# sensors.net
KiCad netlist of a schematic drawn in Altium Designer
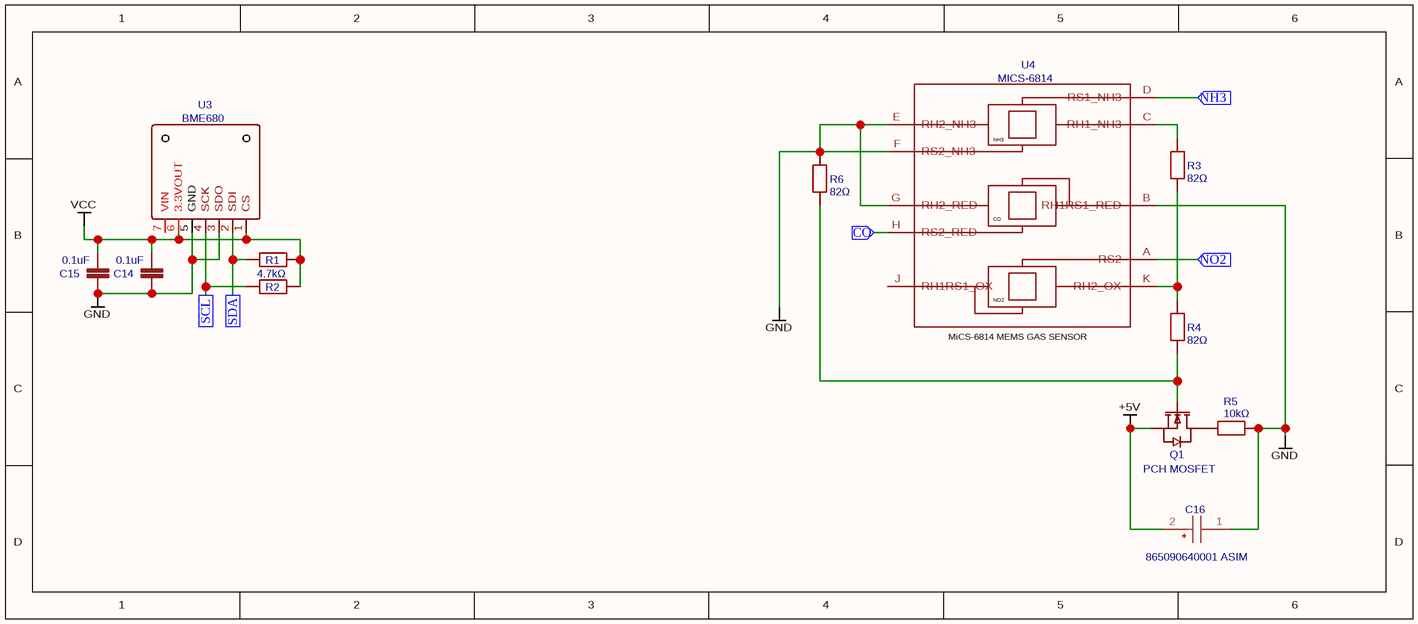
[diagram p0: sensors.schdoc]

(export (version "E")
  (design (tool "Eeschema 10.0.6"))
  (components
    (comp (ref "C14")
      (value "0.1uF")
      (description "CAP-00810")
      (fields (field (name "CONTRIBUTOR") "SparkFun"))
      (libsource (lib "altium-import") (part "root_0_0.1uF_"))
    )
    (comp (ref "C15")
      (value "0.1uF")
      (description "CAP-00810")
      (fields (field (name "CONTRIBUTOR") "SparkFun"))
      (libsource (lib "altium-import") (part "root_0_0.1uF_"))
    )
    (comp (ref "C16")
      (value "865090640001 ASIM")
      (fields (field (name "CONTRIBUTOR") "Rajesh Kumar"))
      (libsource (lib "altium-import") (part "root_2_865090640001 ASIM_"))
    )
    (comp (ref "Q1")
      (value "PCH MOSFET")
      (fields
        (field (name "BOM_SUPPLIER PART") "C516873")
        (field (name "BOM_MANUFACTURER PART") "VB1240B")
        (field (name "CONTRIBUTOR") "LCSC")
      )
      (libsource (lib "altium-import") (part "root_3_PCH MOSFET_"))
    )
    (comp (ref "R1")
      (value "4.7kΩ")
      (fields
        (field (name "BOM_SUPPLIER PART") "C517493")
        (field (name "BOM_MANUFACTURER PART") "TC0350D4701T5H")
        (field (name "CONTRIBUTOR") "LCSC")
      )
      (libsource (lib "altium-import") (part "root_2_4.7kΩ_"))
    )
    (comp (ref "R2")
      (value "4.7kΩ")
      (fields
        (field (name "BOM_SUPPLIER PART") "C517493")
        (field (name "BOM_MANUFACTURER PART") "TC0350D4701T5H")
        (field (name "CONTRIBUTOR") "LCSC")
      )
      (libsource (lib "altium-import") (part "root_2_4.7kΩ_"))
    )
    (comp (ref "R3")
      (value "82Ω")
      (fields
        (field (name "BOM_SUPPLIER PART") "C525388")
        (field (name "BOM_MANUFACTURER PART") "TCTR0603F47K0F3960T")
        (field (name "CONTRIBUTOR") "LCSC")
      )
      (libsource (lib "altium-import") (part "root_1_82Ω_"))
    )
    (comp (ref "R4")
      (value "82Ω")
      (fields
        (field (name "BOM_SUPPLIER PART") "C525388")
        (field (name "BOM_MANUFACTURER PART") "TCTR0603F47K0F3960T")
        (field (name "CONTRIBUTOR") "LCSC")
      )
      (libsource (lib "altium-import") (part "root_1_82Ω_"))
    )
    (comp (ref "R5")
      (value "10kΩ")
      (fields
        (field (name "BOM_SUPPLIER PART") "C525388")
        (field (name "BOM_MANUFACTURER PART") "TCTR0603F47K0F3960T")
        (field (name "CONTRIBUTOR") "LCSC")
      )
      (libsource (lib "altium-import") (part "root_2_10kΩ_"))
    )
    (comp (ref "R6")
      (value "82Ω")
      (fields
        (field (name "BOM_SUPPLIER PART") "C525388")
        (field (name "BOM_MANUFACTURER PART") "TCTR0603F47K0F3960T")
        (field (name "CONTRIBUTOR") "LCSC")
      )
      (libsource (lib "altium-import") (part "root_3_82Ω_"))
    )
    (comp (ref "U3")
      (value "BME680")
      (fields (field (name "BOM_SUPPLIER PART") "C125972") (field (name "CONTRIBUTOR") "mecopela"))
      (libsource (lib "altium-import") (part "root_1_BME680_"))
    )
    (comp (ref "U4")
      (value "MICS-6814")
      (description "314100015")
      (fields (field (name "CONTRIBUTOR") "sozturk"))
      (libsource (lib "altium-import") (part "root_0_MICS-6814_"))
    )
  )
  (nets
    (net (code "1") (name "+5V") (class "Default")
      (node (ref "C16") (pin "2") (pinfunction "-_2") (pintype "passive"))
      (node (ref "Q1") (pin "2") (pinfunction "S_2") (pintype "passive"))
    )
    (net (code "2") (name "/CO") (class "Default")
      (node (ref "U4") (pin "H") (pinfunction "RS2_RED_H") (pintype "passive"))
    )
    (net (code "3") (name "/NH3") (class "Default")
      (node (ref "U4") (pin "D") (pinfunction "RS1_NH3_D") (pintype "passive"))
    )
    (net (code "4") (name "/NO2") (class "Default")
      (node (ref "U4") (pin "A") (pinfunction "RS2_A") (pintype "passive"))
    )
    (net (code "5") (name "/SCL") (class "Default")
      (node (ref "R2") (pin "2") (pinfunction "2_2") (pintype "passive"))
      (node (ref "U3") (pin "4") (pinfunction "SCK_4") (pintype "passive"))
    )
    (net (code "6") (name "/SDA") (class "Default")
      (node (ref "R1") (pin "2") (pinfunction "2_2") (pintype "passive"))
      (node (ref "U3") (pin "2") (pinfunction "SDI_2") (pintype "passive"))
    )
    (net (code "7") (name "GND") (class "Default")
      (node (ref "C14") (pin "2") (pinfunction "2_2") (pintype "passive"))
      (node (ref "C15") (pin "2") (pinfunction "2_2") (pintype "passive"))
      (node (ref "C16") (pin "1") (pinfunction "+_1") (pintype "passive"))
      (node (ref "R5") (pin "1") (pinfunction "1_1") (pintype "passive"))
      (node (ref "R6") (pin "1") (pinfunction "1_1") (pintype "passive"))
      (node (ref "U3") (pin "3") (pinfunction "SDO_3") (pintype "passive"))
      (node (ref "U3") (pin "5") (pinfunction "GND_5") (pintype "passive"))
      (node (ref "U4") (pin "B") (pinfunction "RH1RS1_RED_B") (pintype "passive"))
      (node (ref "U4") (pin "E") (pinfunction "RH2_NH3_E") (pintype "passive"))
      (node (ref "U4") (pin "F") (pinfunction "RS2_NH3_F") (pintype "passive"))
      (node (ref "U4") (pin "G") (pinfunction "RH2_RED_G") (pintype "passive"))
    )
    (net (code "8") (name "Net-(Q1-D)") (class "Default")
      (node (ref "Q1") (pin "3") (pinfunction "D_3") (pintype "passive"))
      (node (ref "R5") (pin "2") (pinfunction "2_2") (pintype "passive"))
    )
    (net (code "9") (name "Net-(Q1-G)") (class "Default")
      (node (ref "Q1") (pin "1") (pinfunction "G_1") (pintype "passive"))
      (node (ref "R4") (pin "1") (pinfunction "1_1") (pintype "passive"))
      (node (ref "R6") (pin "2") (pinfunction "2_2") (pintype "passive"))
    )
    (net (code "10") (name "Net-(U4-RH1_NH3)") (class "Default")
      (node (ref "R3") (pin "2") (pinfunction "2_2") (pintype "passive"))
      (node (ref "U4") (pin "C") (pinfunction "RH1_NH3_C") (pintype "passive"))
    )
    (net (code "11") (name "Net-(U4-RH2_OX)") (class "Default")
      (node (ref "R3") (pin "1") (pinfunction "1_1") (pintype "passive"))
      (node (ref "R4") (pin "2") (pinfunction "2_2") (pintype "passive"))
      (node (ref "U4") (pin "K") (pinfunction "RH2_OX_K") (pintype "passive"))
    )
    (net (code "12") (name "VCC") (class "Default")
      (node (ref "C14") (pin "1") (pinfunction "1_1") (pintype "passive"))
      (node (ref "C15") (pin "1") (pinfunction "1_1") (pintype "passive"))
      (node (ref "R1") (pin "1") (pinfunction "1_1") (pintype "passive"))
      (node (ref "R2") (pin "1") (pinfunction "1_1") (pintype "passive"))
      (node (ref "U3") (pin "1") (pinfunction "CS_1") (pintype "passive"))
      (node (ref "U3") (pin "6") (pinfunction "3.3VOUT_6") (pintype "passive"))
    )
    (net (code "13") (name "unconnected-(U3-VIN-Pad7)") (class "Default")
      (node (ref "U3") (pin "7") (pinfunction "VIN_7") (pintype "passive"))
    )
    (net (code "14") (name "unconnected-(U4-RH1RS1_OX-PadJ)") (class "Default")
      (node (ref "U4") (pin "J") (pinfunction "RH1RS1_OX_J") (pintype "passive"))
    )
  )
)
